# SlideSwitchMCU.net
KiCad netlist of a schematic drawn in Altium Designer
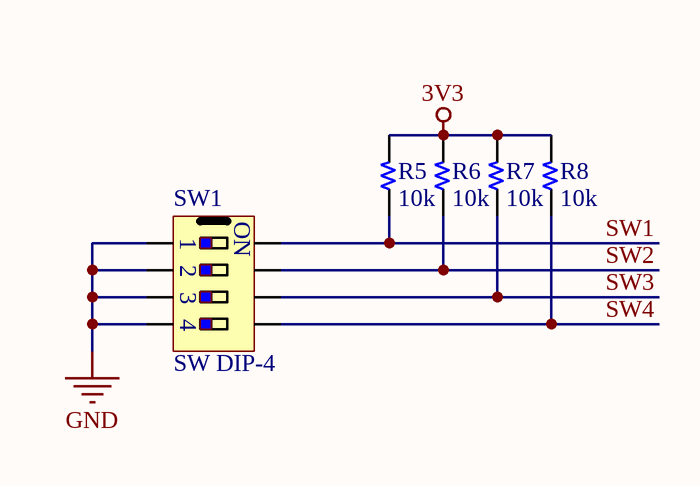
[diagram p0: SlideSwitchMCU.SchDoc]

(export (version "E")
  (design (tool "Eeschema 10.0.6"))
  (components
    (comp (ref "R5")
      (value "10k")
      (footprint "R 0805")
      (description "Resistor")
      (libsource (lib "chipfc_libs") (part "Resistor"))
    )
    (comp (ref "R6")
      (value "10k")
      (footprint "R 0805")
      (description "Resistor")
      (libsource (lib "chipfc_libs") (part "Resistor"))
    )
    (comp (ref "R7")
      (value "10k")
      (footprint "R 0805")
      (description "Resistor")
      (libsource (lib "chipfc_libs") (part "Resistor"))
    )
    (comp (ref "R8")
      (value "10k")
      (footprint "R 0805")
      (description "Resistor")
      (libsource (lib "chipfc_libs") (part "Resistor"))
    )
    (comp (ref "SW1")
      (value "SW DIP-4")
      (footprint "SW/DIP4")
      (libsource (lib "chipfc_libs") (part "SW DIP-4"))
    )
  )
  (nets
    (net (code "1") (name "/SW1") (class "Default")
      (node (ref "R5") (pin "1") (pinfunction "1_1") (pintype "passive"))
      (node (ref "SW1") (pin "8") (pinfunction "8_8") (pintype "passive"))
    )
    (net (code "2") (name "/SW2") (class "Default")
      (node (ref "R6") (pin "1") (pinfunction "1_1") (pintype "passive"))
      (node (ref "SW1") (pin "7") (pinfunction "7_7") (pintype "passive"))
    )
    (net (code "3") (name "/SW3") (class "Default")
      (node (ref "R7") (pin "1") (pinfunction "1_1") (pintype "passive"))
      (node (ref "SW1") (pin "6") (pinfunction "6_6") (pintype "passive"))
    )
    (net (code "4") (name "/SW4") (class "Default")
      (node (ref "R8") (pin "1") (pinfunction "1_1") (pintype "passive"))
      (node (ref "SW1") (pin "5") (pinfunction "5_5") (pintype "passive"))
    )
    (net (code "5") (name "3V3") (class "Default")
      (node (ref "R5") (pin "2") (pinfunction "2_2") (pintype "passive"))
      (node (ref "R6") (pin "2") (pinfunction "2_2") (pintype "passive"))
      (node (ref "R7") (pin "2") (pinfunction "2_2") (pintype "passive"))
      (node (ref "R8") (pin "2") (pinfunction "2_2") (pintype "passive"))
    )
    (net (code "6") (name "GND") (class "Default")
      (node (ref "SW1") (pin "1") (pinfunction "1_1") (pintype "passive"))
      (node (ref "SW1") (pin "2") (pinfunction "2_2") (pintype "passive"))
      (node (ref "SW1") (pin "3") (pinfunction "3_3") (pintype "passive"))
      (node (ref "SW1") (pin "4") (pinfunction "4_4") (pintype "passive"))
    )
  )
)
